# SCH_firebase_esp8266_2024-04-16.net
KiCad netlist of a schematic drawn in EasyEDA
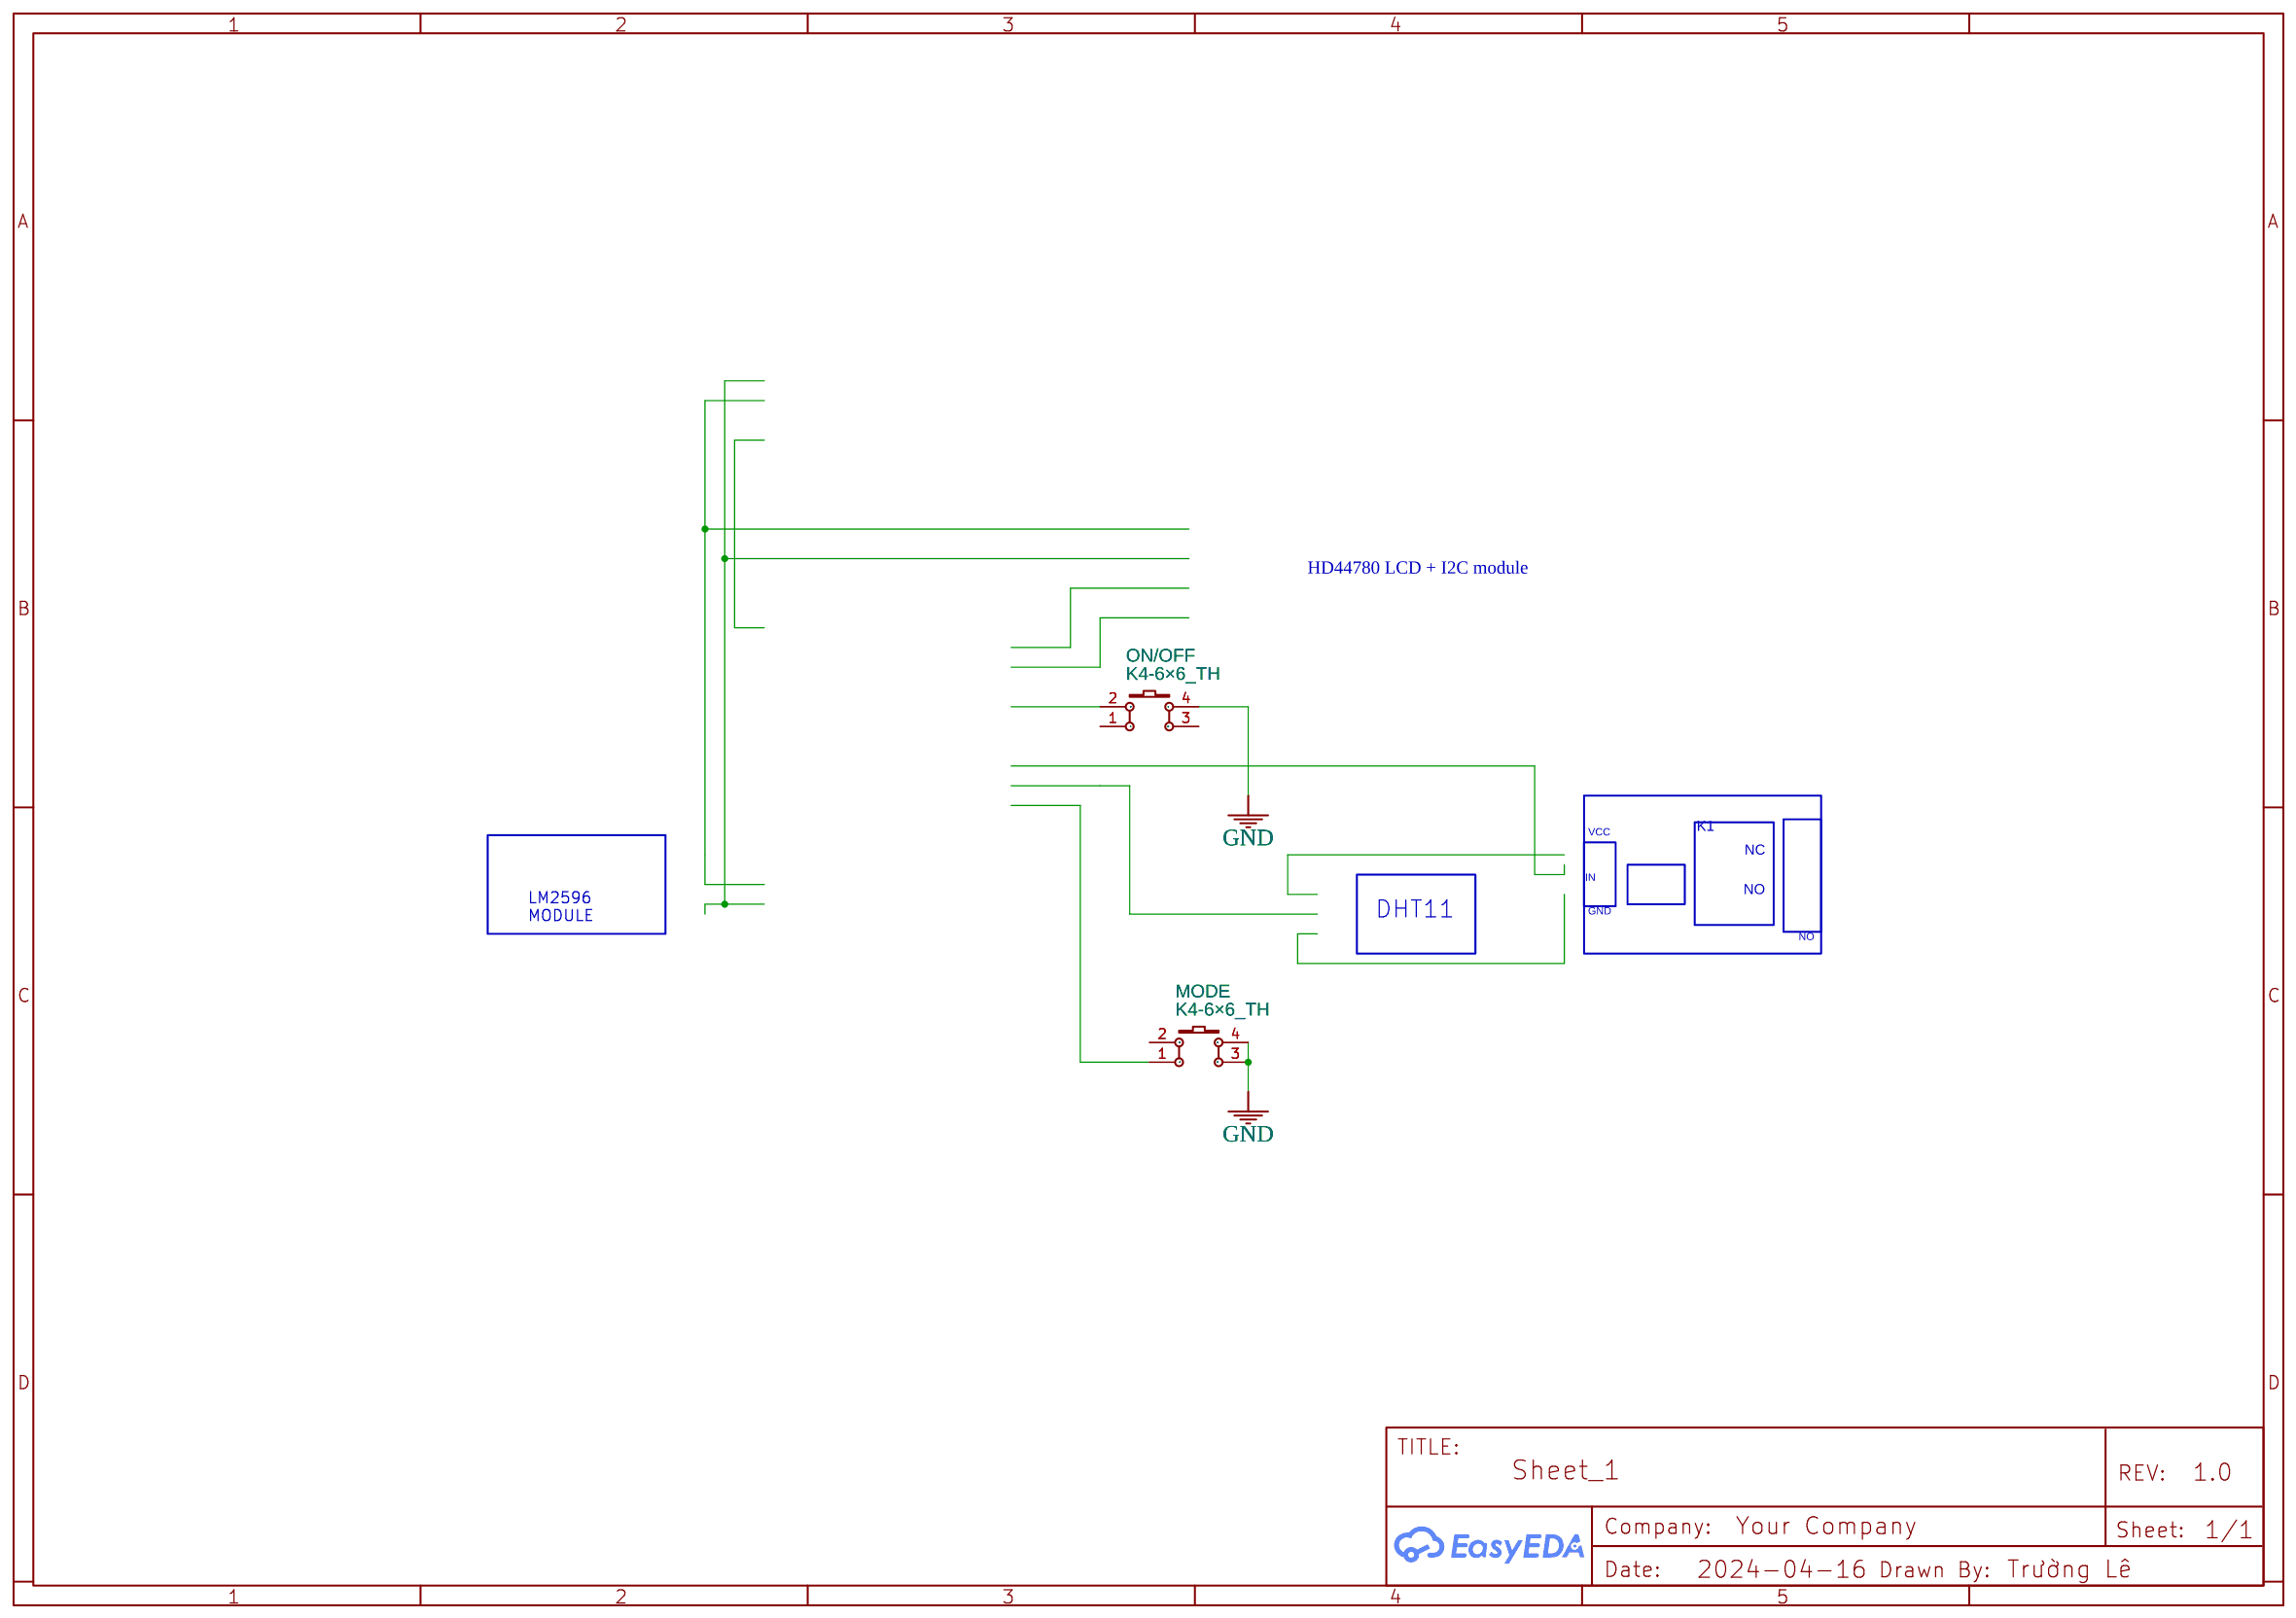
[diagram p0: schematic sheet]

(export (version "E")
  (design (tool "Eeschema 10.0.6"))
  (components
    (comp (ref "MODE")
      (value "K4-6×6_TH")
      (fields (field (name "Manufacturer Part") "K2-1102DP-E4SW-04") (field (name "Manufacturer") "韩国韩荣"))
      (libsource (lib "") (part "K4-6×6_TH_1"))
    )
    (comp (ref "ON/OFF")
      (value "K4-6×6_TH")
      (fields (field (name "Manufacturer Part") "K2-1102DP-E4SW-04") (field (name "Manufacturer") "韩国韩荣"))
      (libsource (lib "") (part "K4-6×6_TH"))
    )
  )
  (nets
    (net (code "1") (name "GND") (class "Default")
      (node (ref "MODE") (pin "3") (pinfunction "3_3") (pintype "unspecified"))
      (node (ref "MODE") (pin "4") (pinfunction "4_4") (pintype "unspecified"))
      (node (ref "ON/OFF") (pin "4") (pinfunction "4_4") (pintype "unspecified"))
    )
    (net (code "2") (name "unconnected-(MODE-Pad1)") (class "Default")
      (node (ref "MODE") (pin "1") (pinfunction "1_1") (pintype "unspecified"))
    )
    (net (code "3") (name "unconnected-(MODE-Pad2)") (class "Default")
      (node (ref "MODE") (pin "2") (pinfunction "2_2") (pintype "unspecified"))
    )
    (net (code "4") (name "unconnected-(ON/OFF-Pad1)") (class "Default")
      (node (ref "ON/OFF") (pin "1") (pinfunction "1_1") (pintype "unspecified"))
    )
    (net (code "5") (name "unconnected-(ON/OFF-Pad2)") (class "Default")
      (node (ref "ON/OFF") (pin "2") (pinfunction "2_2") (pintype "unspecified"))
    )
    (net (code "6") (name "unconnected-(ON/OFF-Pad3)") (class "Default")
      (node (ref "ON/OFF") (pin "3") (pinfunction "3_3") (pintype "unspecified"))
    )
  )
)
